# db25.net
KiCad netlist of a schematic drawn in Altium Designer
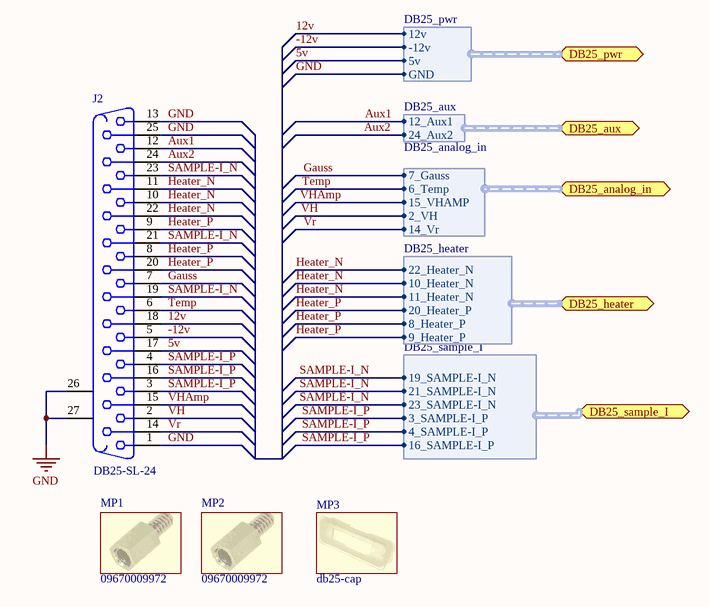
[diagram p0: db25.SchDoc]

(export (version "E")
  (design (tool "Eeschema 10.0.6"))
  (components
    (comp (ref "J2")
      (value "~")
      (footprint "custom_components:DB25")
      (description "d-sub, 25 pins,  Right Angle")
      (fields
        (field (name "MANUFACTURER") "ADAM TECH")
        (field (name "MANUFACTURER PART NUMBER") "DB25-SL-24")
      )
      (libsource (lib "Miscellaneous Connectors") (part "D Connector 25"))
    )
    (comp (ref "MP1")
      (value "09670009972")
      (fields (field (name "MANUFACTURER") "HARTING"))
      (libsource (lib "custom_components") (part "09670009972"))
    )
    (comp (ref "MP2")
      (value "09670009972")
      (fields (field (name "MANUFACTURER") "HARTING"))
      (libsource (lib "custom_components") (part "09670009972"))
    )
    (comp (ref "MP3")
      (value "db25-cap")
      (fields
        (field (name "MANUFACTURER PART NUMBER") "2105-0100-03")
        (field (name "MANUFACTURER") "Encitech")
      )
      (libsource (lib "custom_components") (part "db25-cap"))
    )
  )
  (nets
    (net (code "6") (name "/-12v") (class "Default")
      (node (ref "J2") (pin "5") (pinfunction "5_5") (pintype "passive"))
    )
    (net (code "7") (name "/5v") (class "Default")
      (node (ref "J2") (pin "17") (pinfunction "17_17") (pintype "passive"))
    )
    (net (code "8") (name "/12v") (class "Default")
      (node (ref "J2") (pin "18") (pinfunction "18_18") (pintype "passive"))
    )
    (net (code "9") (name "/Aux1") (class "Default")
      (node (ref "J2") (pin "12") (pinfunction "12_12") (pintype "passive"))
    )
    (net (code "10") (name "/Aux2") (class "Default")
      (node (ref "J2") (pin "24") (pinfunction "24_24") (pintype "passive"))
    )
    (net (code "11") (name "/Gauss") (class "Default")
      (node (ref "J2") (pin "7") (pinfunction "7_7") (pintype "passive"))
    )
    (net (code "12") (name "/Heater_N") (class "Default")
      (node (ref "J2") (pin "10") (pinfunction "10_10") (pintype "passive"))
      (node (ref "J2") (pin "11") (pinfunction "11_11") (pintype "passive"))
      (node (ref "J2") (pin "22") (pinfunction "22_22") (pintype "passive"))
    )
    (net (code "13") (name "/Heater_P") (class "Default")
      (node (ref "J2") (pin "20") (pinfunction "20_20") (pintype "passive"))
      (node (ref "J2") (pin "8") (pinfunction "8_8") (pintype "passive"))
      (node (ref "J2") (pin "9") (pinfunction "9_9") (pintype "passive"))
    )
    (net (code "14") (name "/SAMPLE-I_N") (class "Default")
      (node (ref "J2") (pin "19") (pinfunction "19_19") (pintype "passive"))
      (node (ref "J2") (pin "21") (pinfunction "21_21") (pintype "passive"))
      (node (ref "J2") (pin "23") (pinfunction "23_23") (pintype "passive"))
    )
    (net (code "15") (name "/SAMPLE-I_P") (class "Default")
      (node (ref "J2") (pin "16") (pinfunction "16_16") (pintype "passive"))
      (node (ref "J2") (pin "3") (pinfunction "3_3") (pintype "passive"))
      (node (ref "J2") (pin "4") (pinfunction "4_4") (pintype "passive"))
    )
    (net (code "16") (name "/Temp") (class "Default")
      (node (ref "J2") (pin "6") (pinfunction "6_6") (pintype "passive"))
    )
    (net (code "17") (name "/VH") (class "Default")
      (node (ref "J2") (pin "2") (pinfunction "2_2") (pintype "passive"))
    )
    (net (code "18") (name "/VHAmp") (class "Default")
      (node (ref "J2") (pin "15") (pinfunction "15_15") (pintype "passive"))
    )
    (net (code "19") (name "/Vr") (class "Default")
      (node (ref "J2") (pin "14") (pinfunction "14_14") (pintype "passive"))
    )
    (net (code "25") (name "GND") (class "Default")
      (node (ref "J2") (pin "1") (pinfunction "1_1") (pintype "passive"))
      (node (ref "J2") (pin "13") (pinfunction "13_13") (pintype "passive"))
      (node (ref "J2") (pin "25") (pinfunction "25_25") (pintype "passive"))
      (node (ref "J2") (pin "26") (pinfunction "MH1_26") (pintype "passive"))
      (node (ref "J2") (pin "27") (pinfunction "MH2_27") (pintype "passive"))
    )
  )
)
